# rev2.net
KiCad netlist of a schematic drawn in EAGLE
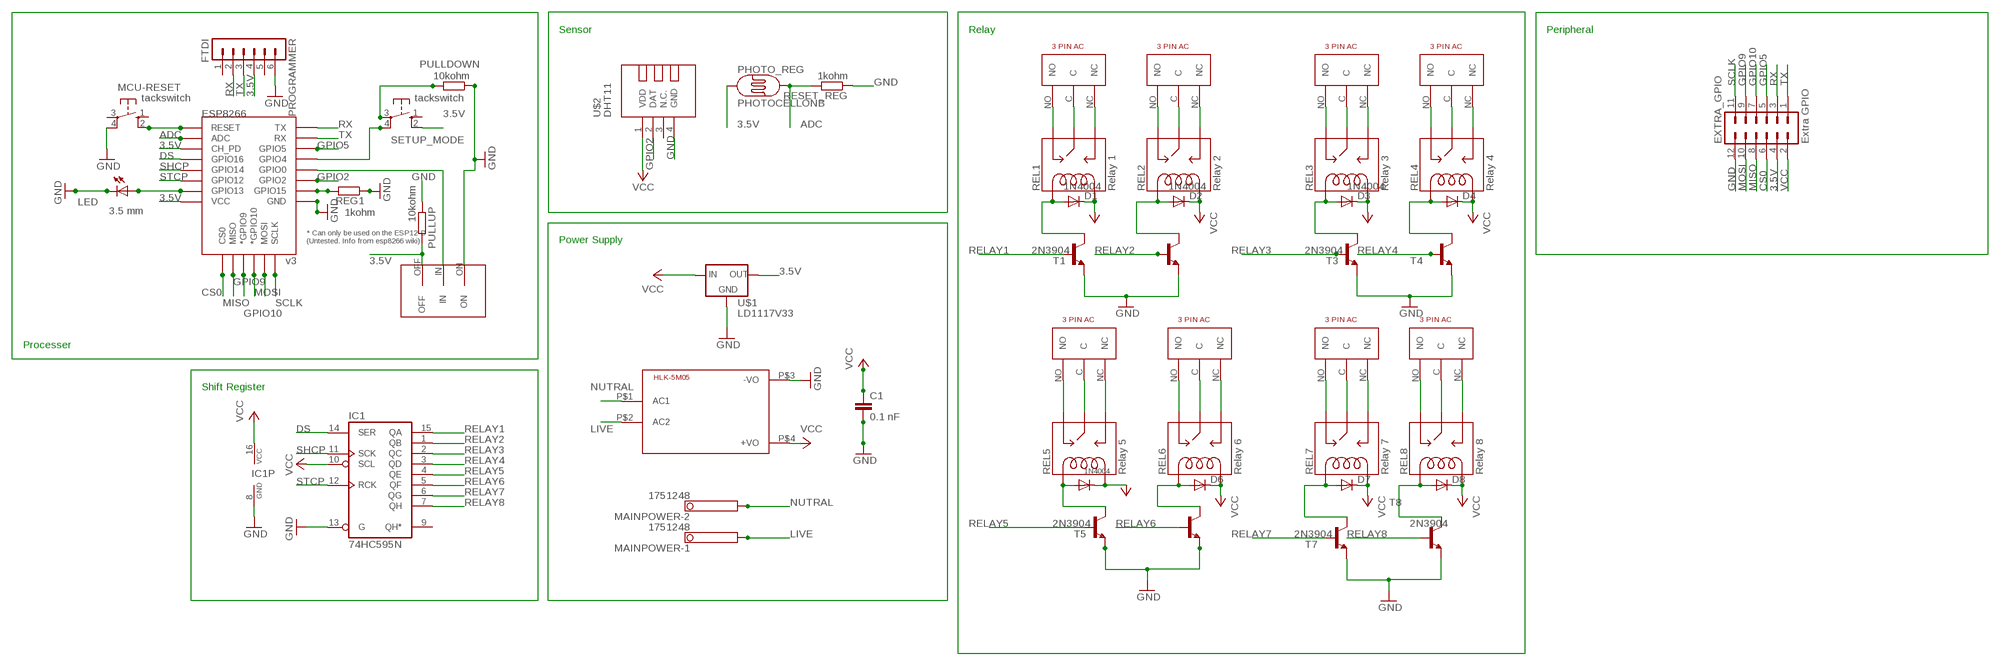
[diagram p0: schematic, sheet 1]

(export (version "E")
  (design (tool "Eeschema 10.0.6"))
  (components
    (comp (ref "C1")
      (value "0.1 nF")
      (footprint "eagle-import:CAP-PTH-SMALL-KIT")
      (libsource (lib "eagle-import") (part "0.1UF-KIT-EZ-50V-20%"))
    )
    (comp (ref "CON-REL-1")
      (value "3PINAC")
      (footprint "eagle-import:LIB")
      (libsource (lib "eagle-import") (part "3PINAC"))
    )
    (comp (ref "CON-REL-2")
      (value "3PINAC")
      (footprint "eagle-import:LIB")
      (libsource (lib "eagle-import") (part "3PINAC"))
    )
    (comp (ref "CON-REL-3")
      (value "3PINAC")
      (footprint "eagle-import:LIB")
      (libsource (lib "eagle-import") (part "3PINAC"))
    )
    (comp (ref "CON-REL-4")
      (value "3PINAC")
      (footprint "eagle-import:LIB")
      (libsource (lib "eagle-import") (part "3PINAC"))
    )
    (comp (ref "CON-REL-5")
      (value "3PINAC")
      (footprint "eagle-import:LIB")
      (libsource (lib "eagle-import") (part "3PINAC"))
    )
    (comp (ref "CON-REL-6")
      (value "3PINAC")
      (footprint "eagle-import:LIB")
      (libsource (lib "eagle-import") (part "3PINAC"))
    )
    (comp (ref "CON-REL-7")
      (value "3PINAC")
      (footprint "eagle-import:LIB")
      (libsource (lib "eagle-import") (part "3PINAC"))
    )
    (comp (ref "CON-REL-8")
      (value "3PINAC")
      (footprint "eagle-import:LIB")
      (libsource (lib "eagle-import") (part "3PINAC"))
    )
    (comp (ref "D1")
      (value "1N4004")
      (footprint "eagle-import:DO41-10")
      (libsource (lib "eagle-import") (part "1N4004"))
    )
    (comp (ref "D2")
      (value "1N4004")
      (footprint "eagle-import:DO41-10")
      (libsource (lib "eagle-import") (part "1N4004"))
    )
    (comp (ref "D3")
      (value "1N4004")
      (footprint "eagle-import:DO41-10")
      (libsource (lib "eagle-import") (part "1N4004"))
    )
    (comp (ref "D4")
      (value "1N4004")
      (footprint "eagle-import:DO41-10")
      (libsource (lib "eagle-import") (part "1N4004"))
    )
    (comp (ref "D5")
      (value "1N4004")
      (footprint "eagle-import:DO41-10")
      (libsource (lib "eagle-import") (part "1N4004"))
    )
    (comp (ref "D6")
      (value "1N4004")
      (footprint "eagle-import:DO41-10")
      (libsource (lib "eagle-import") (part "1N4004"))
    )
    (comp (ref "D7")
      (value "1N4004")
      (footprint "eagle-import:DO41-10")
      (libsource (lib "eagle-import") (part "1N4004"))
    )
    (comp (ref "D8")
      (value "1N4004")
      (footprint "eagle-import:DO41-10")
      (libsource (lib "eagle-import") (part "1N4004"))
    )
    (comp (ref "ESP8266")
      (value "v3")
      (footprint "eagle-import:ESP12E-SMD")
      (libsource (lib "eagle-import") (part "ESP12ESMD"))
    )
    (comp (ref "EXTRA_GPIO")
      (value "Extra GPIO")
      (footprint "eagle-import:MA06-2")
      (libsource (lib "eagle-import") (part "MA06-2"))
    )
    (comp (ref "FLASH")
      (value "TOGGLE_SWITCH")
      (footprint "eagle-import:TOGGLE_SWITCH")
      (libsource (lib "eagle-import") (part "TOGGLE_SWITCH"))
    )
    (comp (ref "HLK-5M05")
      (value "AC to DC Converter")
      (footprint "eagle-import:HKLPM01")
      (libsource (lib "eagle-import") (part "HKLPM01"))
    )
    (comp (ref "IC1")
      (value "74HC595N")
      (footprint "eagle-import:DIL16")
      (libsource (lib "eagle-import") (part "74595NHC"))
    )
    (comp (ref "LED")
      (value "3.5 mm")
      (footprint "eagle-import:LED3MM")
      (libsource (lib "eagle-import") (part "LED3MM"))
    )
    (comp (ref "MAINPOWER")
      (value "1751248")
      (footprint "eagle-import:1751248")
      (libsource (lib "eagle-import") (part "1751248"))
    )
    (comp (ref "MCU-RESET")
      (value "tackswitch")
      (footprint "eagle-import:B3F-10XX")
      (libsource (lib "eagle-import") (part "10-XX"))
    )
    (comp (ref "PHOTO_REG")
      (value "PHOTOCELLONB")
      (footprint "eagle-import:ON_BOARD")
      (libsource (lib "eagle-import") (part "PHOTOCELLONB"))
    )
    (comp (ref "PROGRAMMER")
      (value "FTDI")
      (footprint "eagle-import:MA06-1")
      (libsource (lib "eagle-import") (part "MA06-1"))
    )
    (comp (ref "PULLDOWN")
      (value "10kohm")
      (footprint "eagle-import:0204_7")
      (libsource (lib "eagle-import") (part "R-EU_0204/7"))
    )
    (comp (ref "PULLUP")
      (value "10kohm")
      (footprint "eagle-import:0204_7")
      (libsource (lib "eagle-import") (part "R-EU_0204/7"))
    )
    (comp (ref "REG1")
      (value "1kohm")
      (footprint "eagle-import:0204_7")
      (libsource (lib "eagle-import") (part "R-EU_0204/7"))
    )
    (comp (ref "REL1")
      (value "Relay 1")
      (footprint "eagle-import:SRD-05VDC-SL-C")
      (libsource (lib "eagle-import") (part "RELAYPTH"))
    )
    (comp (ref "REL2")
      (value "Relay 2")
      (footprint "eagle-import:SRD-05VDC-SL-C")
      (libsource (lib "eagle-import") (part "RELAYPTH"))
    )
    (comp (ref "REL3")
      (value "Relay 3")
      (footprint "eagle-import:SRD-05VDC-SL-C")
      (libsource (lib "eagle-import") (part "RELAYPTH"))
    )
    (comp (ref "REL4")
      (value "Relay 4")
      (footprint "eagle-import:SRD-05VDC-SL-C")
      (libsource (lib "eagle-import") (part "RELAYPTH"))
    )
    (comp (ref "REL5")
      (value "Relay 5")
      (footprint "eagle-import:SRD-05VDC-SL-C")
      (libsource (lib "eagle-import") (part "RELAYPTH"))
    )
    (comp (ref "REL6")
      (value "Relay 6")
      (footprint "eagle-import:SRD-05VDC-SL-C")
      (libsource (lib "eagle-import") (part "RELAYPTH"))
    )
    (comp (ref "REL7")
      (value "Relay 7")
      (footprint "eagle-import:SRD-05VDC-SL-C")
      (libsource (lib "eagle-import") (part "RELAYPTH"))
    )
    (comp (ref "REL8")
      (value "Relay 8")
      (footprint "eagle-import:SRD-05VDC-SL-C")
      (libsource (lib "eagle-import") (part "RELAYPTH"))
    )
    (comp (ref "RESET_REG")
      (value "1kohm")
      (footprint "eagle-import:0204_7")
      (libsource (lib "eagle-import") (part "R-EU_0204/7"))
    )
    (comp (ref "SETUP_MODE")
      (value "tackswitch")
      (footprint "eagle-import:B3F-10XX")
      (libsource (lib "eagle-import") (part "10-XX"))
    )
    (comp (ref "T1")
      (value "2N3904")
      (footprint "eagle-import:TO92-EBC")
      (libsource (lib "eagle-import") (part "BC618"))
    )
    (comp (ref "T2")
      (value "2N3904")
      (footprint "eagle-import:TO92-EBC")
      (libsource (lib "eagle-import") (part "BC618"))
    )
    (comp (ref "T3")
      (value "2N3904")
      (footprint "eagle-import:TO92-EBC")
      (libsource (lib "eagle-import") (part "BC618"))
    )
    (comp (ref "T4")
      (value "2N3904")
      (footprint "eagle-import:TO92-EBC")
      (libsource (lib "eagle-import") (part "BC618"))
    )
    (comp (ref "T5")
      (value "2N3904")
      (footprint "eagle-import:TO92-EBC")
      (libsource (lib "eagle-import") (part "BC618"))
    )
    (comp (ref "T6")
      (value "2N3904")
      (footprint "eagle-import:TO92-EBC")
      (libsource (lib "eagle-import") (part "BC618"))
    )
    (comp (ref "T7")
      (value "2N3904")
      (footprint "eagle-import:TO92-EBC")
      (libsource (lib "eagle-import") (part "BC618"))
    )
    (comp (ref "T8")
      (value "2N3904")
      (footprint "eagle-import:TO92-EBC")
      (libsource (lib "eagle-import") (part "BC618"))
    )
    (comp (ref "U$1")
      (value "LD1117V33")
      (footprint "eagle-import:LD1117V33")
      (libsource (lib "eagle-import") (part "LD1117V33"))
    )
    (comp (ref "U$2")
      (value "DHT11")
      (footprint "eagle-import:TEMP-HUM-SENSOR-DHT11")
      (libsource (lib "eagle-import") (part "TEMP-HUM-SENSOR-DHT11"))
    )
  )
  (nets
    (net (code "1") (name "/3.5V") (class "Default")
      (node (ref "ESP8266") (pin "CH_PD") (pinfunction "CH_PD_CH_PD") (pintype "bidirectional"))
      (node (ref "ESP8266") (pin "VCC") (pinfunction "VCC_VCC") (pintype "bidirectional"))
      (node (ref "EXTRA_GPIO") (pin "4") (pinfunction "4_4") (pintype "passive"))
      (node (ref "FLASH") (pin "OFF") (pinfunction "OFF_OFF") (pintype "bidirectional"))
      (node (ref "PHOTO_REG") (pin "1") (pinfunction "P$1_1") (pintype "bidirectional"))
      (node (ref "PROGRAMMER") (pin "4") (pinfunction "4_4") (pintype "passive"))
      (node (ref "PULLUP") (pin "2") (pinfunction "2_2") (pintype "passive"))
      (node (ref "SETUP_MODE") (pin "2") (pinfunction "S1_2") (pintype "passive"))
      (node (ref "U$1") (pin "OUT") (pinfunction "OUT_OUT") (pintype "output"))
    )
    (net (code "2") (name "/ADC") (class "Default")
      (node (ref "ESP8266") (pin "ADC") (pinfunction "ADC_ADC") (pintype "bidirectional"))
      (node (ref "PHOTO_REG") (pin "2") (pinfunction "P$2_2") (pintype "bidirectional"))
      (node (ref "RESET_REG") (pin "2") (pinfunction "2_2") (pintype "passive"))
    )
    (net (code "3") (name "/CS0") (class "Default")
      (node (ref "ESP8266") (pin "CS0") (pinfunction "CS0_CS0") (pintype "bidirectional"))
      (node (ref "EXTRA_GPIO") (pin "6") (pinfunction "6_6") (pintype "passive"))
    )
    (net (code "4") (name "/DS") (class "Default")
      (node (ref "ESP8266") (pin "GPIO16") (pinfunction "GPIO16_GPIO16") (pintype "bidirectional"))
      (node (ref "IC1") (pin "14") (pinfunction "SER_14") (pintype "input"))
    )
    (net (code "5") (name "/GPIO2") (class "Default")
      (node (ref "ESP8266") (pin "GPIO2") (pinfunction "GPIO2_GPIO2") (pintype "bidirectional"))
      (node (ref "U$2") (pin "2") (pinfunction "DAT_2") (pintype "bidirectional"))
    )
    (net (code "6") (name "/GPIO5") (class "Default")
      (node (ref "ESP8266") (pin "GPIO5") (pinfunction "GPIO5_GPIO5") (pintype "bidirectional"))
      (node (ref "EXTRA_GPIO") (pin "5") (pinfunction "5_5") (pintype "passive"))
    )
    (net (code "7") (name "/GPIO9") (class "Default")
      (node (ref "ESP8266") (pin "GPIO9") (pinfunction "*GPIO9_GPIO9") (pintype "bidirectional"))
      (node (ref "EXTRA_GPIO") (pin "9") (pinfunction "9_9") (pintype "passive"))
    )
    (net (code "8") (name "/GPIO10") (class "Default")
      (node (ref "ESP8266") (pin "GPIO10") (pinfunction "*GPIO10_GPIO10") (pintype "bidirectional"))
      (node (ref "EXTRA_GPIO") (pin "7") (pinfunction "7_7") (pintype "passive"))
    )
    (net (code "9") (name "/LIVE") (class "Default")
      (node (ref "HLK-5M05") (pin "P$2") (pinfunction "AC2_P$2") (pintype "bidirectional"))
      (node (ref "MAINPOWER") (pin "1") (pinfunction "K_1") (pintype "passive"))
    )
    (net (code "10") (name "/MISO") (class "Default")
      (node (ref "ESP8266") (pin "MISO") (pinfunction "MISO_MISO") (pintype "bidirectional"))
      (node (ref "EXTRA_GPIO") (pin "8") (pinfunction "8_8") (pintype "passive"))
    )
    (net (code "11") (name "/MOSI") (class "Default")
      (node (ref "ESP8266") (pin "MOSI") (pinfunction "MOSI_MOSI") (pintype "bidirectional"))
      (node (ref "EXTRA_GPIO") (pin "10") (pinfunction "10_10") (pintype "passive"))
    )
    (net (code "12") (name "/NUTRAL") (class "Default")
      (node (ref "HLK-5M05") (pin "P$1") (pinfunction "AC1_P$1") (pintype "bidirectional"))
      (node (ref "MAINPOWER") (pin "2") (pinfunction "K_2") (pintype "passive"))
    )
    (net (code "13") (name "/RELAY1") (class "Default")
      (node (ref "IC1") (pin "15") (pinfunction "QA_15") (pintype "tri_state"))
      (node (ref "T1") (pin "B") (pinfunction "B_B") (pintype "passive"))
    )
    (net (code "14") (name "/RELAY2") (class "Default")
      (node (ref "IC1") (pin "1") (pinfunction "QB_1") (pintype "tri_state"))
      (node (ref "T2") (pin "B") (pinfunction "B_B") (pintype "passive"))
    )
    (net (code "15") (name "/RELAY3") (class "Default")
      (node (ref "IC1") (pin "2") (pinfunction "QC_2") (pintype "tri_state"))
      (node (ref "T3") (pin "B") (pinfunction "B_B") (pintype "passive"))
    )
    (net (code "16") (name "/RELAY4") (class "Default")
      (node (ref "IC1") (pin "3") (pinfunction "QD_3") (pintype "tri_state"))
      (node (ref "T4") (pin "B") (pinfunction "B_B") (pintype "passive"))
    )
    (net (code "17") (name "/RELAY5") (class "Default")
      (node (ref "IC1") (pin "4") (pinfunction "QE_4") (pintype "tri_state"))
      (node (ref "T5") (pin "B") (pinfunction "B_B") (pintype "passive"))
    )
    (net (code "18") (name "/RELAY6") (class "Default")
      (node (ref "IC1") (pin "5") (pinfunction "QF_5") (pintype "tri_state"))
      (node (ref "T6") (pin "B") (pinfunction "B_B") (pintype "passive"))
    )
    (net (code "19") (name "/RELAY7") (class "Default")
      (node (ref "IC1") (pin "6") (pinfunction "QG_6") (pintype "tri_state"))
      (node (ref "T7") (pin "B") (pinfunction "B_B") (pintype "passive"))
    )
    (net (code "20") (name "/RELAY8") (class "Default")
      (node (ref "IC1") (pin "7") (pinfunction "QH_7") (pintype "tri_state"))
      (node (ref "T8") (pin "B") (pinfunction "B_B") (pintype "passive"))
    )
    (net (code "21") (name "/RX") (class "Default")
      (node (ref "ESP8266") (pin "TXD0") (pinfunction "TX_TXD0") (pintype "bidirectional"))
      (node (ref "EXTRA_GPIO") (pin "3") (pinfunction "3_3") (pintype "passive"))
      (node (ref "PROGRAMMER") (pin "2") (pinfunction "2_2") (pintype "passive"))
    )
    (net (code "22") (name "/SCLK") (class "Default")
      (node (ref "ESP8266") (pin "SCLK") (pinfunction "SCLK_SCLK") (pintype "bidirectional"))
      (node (ref "EXTRA_GPIO") (pin "11") (pinfunction "11_11") (pintype "passive"))
    )
    (net (code "23") (name "/SHCP") (class "Default")
      (node (ref "ESP8266") (pin "GPIO14") (pinfunction "GPIO14_GPIO14") (pintype "bidirectional"))
      (node (ref "IC1") (pin "11") (pinfunction "SCK_11") (pintype "input"))
    )
    (net (code "24") (name "/STCP") (class "Default")
      (node (ref "ESP8266") (pin "GPIO12") (pinfunction "GPIO12_GPIO12") (pintype "bidirectional"))
      (node (ref "IC1") (pin "12") (pinfunction "RCK_12") (pintype "input"))
    )
    (net (code "25") (name "/TX") (class "Default")
      (node (ref "ESP8266") (pin "RXD0") (pinfunction "RX_RXD0") (pintype "bidirectional"))
      (node (ref "EXTRA_GPIO") (pin "1") (pinfunction "1_1") (pintype "passive"))
      (node (ref "PROGRAMMER") (pin "3") (pinfunction "3_3") (pintype "passive"))
    )
    (net (code "26") (name "GND") (class "Default")
      (node (ref "C1") (pin "2") (pinfunction "2_2") (pintype "passive"))
      (node (ref "ESP8266") (pin "GND") (pinfunction "GND_GND") (pintype "bidirectional"))
      (node (ref "EXTRA_GPIO") (pin "12") (pinfunction "12_12") (pintype "passive"))
      (node (ref "FLASH") (pin "ON") (pinfunction "ON_ON") (pintype "bidirectional"))
      (node (ref "HLK-5M05") (pin "P$3") (pinfunction "-VO_P$3") (pintype "bidirectional"))
      (node (ref "IC1") (pin "13") (pinfunction "G_13") (pintype "input"))
      (node (ref "IC1") (pin "8") (pinfunction "GND_8") (pintype "power_in"))
      (node (ref "LED") (pin "K") (pinfunction "C_K") (pintype "passive"))
      (node (ref "MCU-RESET") (pin "4") (pinfunction "P1_4") (pintype "passive"))
      (node (ref "PROGRAMMER") (pin "6") (pinfunction "6_6") (pintype "passive"))
      (node (ref "PULLDOWN") (pin "1") (pinfunction "1_1") (pintype "passive"))
      (node (ref "PULLUP") (pin "1") (pinfunction "1_1") (pintype "passive"))
      (node (ref "REG1") (pin "1") (pinfunction "1_1") (pintype "passive"))
      (node (ref "RESET_REG") (pin "1") (pinfunction "1_1") (pintype "passive"))
      (node (ref "T1") (pin "E") (pinfunction "E_E") (pintype "passive"))
      (node (ref "T2") (pin "E") (pinfunction "E_E") (pintype "passive"))
      (node (ref "T3") (pin "E") (pinfunction "E_E") (pintype "passive"))
      (node (ref "T4") (pin "E") (pinfunction "E_E") (pintype "passive"))
      (node (ref "T5") (pin "E") (pinfunction "E_E") (pintype "passive"))
      (node (ref "T6") (pin "E") (pinfunction "E_E") (pintype "passive"))
      (node (ref "T7") (pin "E") (pinfunction "E_E") (pintype "passive"))
      (node (ref "T8") (pin "E") (pinfunction "E_E") (pintype "passive"))
      (node (ref "U$1") (pin "GND") (pinfunction "GND_GND") (pintype "input"))
      (node (ref "U$2") (pin "4") (pinfunction "GND_4") (pintype "power_in"))
    )
    (net (code "27") (name "Net-(CON-REL-1-PadC)") (class "Default")
      (node (ref "CON-REL-1") (pin "C") (pinfunction "C_C") (pintype "bidirectional"))
      (node (ref "REL1") (pin "SWCOMMON") (pinfunction "SWCOMMON_SWCOMMON") (pintype "bidirectional"))
    )
    (net (code "28") (name "Net-(CON-REL-1-PadNC)") (class "Default")
      (node (ref "CON-REL-1") (pin "NC") (pinfunction "NC_NC") (pintype "bidirectional"))
      (node (ref "REL1") (pin "SWOPEN") (pinfunction "SWOPEN_SWOPEN") (pintype "bidirectional"))
    )
    (net (code "29") (name "Net-(CON-REL-2-PadC)") (class "Default")
      (node (ref "CON-REL-2") (pin "C") (pinfunction "C_C") (pintype "bidirectional"))
      (node (ref "REL2") (pin "SWCOMMON") (pinfunction "SWCOMMON_SWCOMMON") (pintype "bidirectional"))
    )
    (net (code "30") (name "Net-(CON-REL-2-PadNC)") (class "Default")
      (node (ref "CON-REL-2") (pin "NC") (pinfunction "NC_NC") (pintype "bidirectional"))
      (node (ref "REL2") (pin "SWOPEN") (pinfunction "SWOPEN_SWOPEN") (pintype "bidirectional"))
    )
    (net (code "31") (name "Net-(CON-REL-3-PadC)") (class "Default")
      (node (ref "CON-REL-3") (pin "C") (pinfunction "C_C") (pintype "bidirectional"))
      (node (ref "REL3") (pin "SWCOMMON") (pinfunction "SWCOMMON_SWCOMMON") (pintype "bidirectional"))
    )
    (net (code "32") (name "Net-(CON-REL-3-PadNC)") (class "Default")
      (node (ref "CON-REL-3") (pin "NC") (pinfunction "NC_NC") (pintype "bidirectional"))
      (node (ref "REL3") (pin "SWOPEN") (pinfunction "SWOPEN_SWOPEN") (pintype "bidirectional"))
    )
    (net (code "33") (name "Net-(CON-REL-4-PadC)") (class "Default")
      (node (ref "CON-REL-4") (pin "C") (pinfunction "C_C") (pintype "bidirectional"))
      (node (ref "REL4") (pin "SWCOMMON") (pinfunction "SWCOMMON_SWCOMMON") (pintype "bidirectional"))
    )
    (net (code "34") (name "Net-(CON-REL-4-PadNC)") (class "Default")
      (node (ref "CON-REL-4") (pin "NC") (pinfunction "NC_NC") (pintype "bidirectional"))
      (node (ref "REL4") (pin "SWOPEN") (pinfunction "SWOPEN_SWOPEN") (pintype "bidirectional"))
    )
    (net (code "35") (name "Net-(CON-REL-5-PadC)") (class "Default")
      (node (ref "CON-REL-5") (pin "C") (pinfunction "C_C") (pintype "bidirectional"))
      (node (ref "REL5") (pin "SWCOMMON") (pinfunction "SWCOMMON_SWCOMMON") (pintype "bidirectional"))
    )
    (net (code "36") (name "Net-(CON-REL-5-PadNC)") (class "Default")
      (node (ref "CON-REL-5") (pin "NC") (pinfunction "NC_NC") (pintype "bidirectional"))
      (node (ref "REL5") (pin "SWOPEN") (pinfunction "SWOPEN_SWOPEN") (pintype "bidirectional"))
    )
    (net (code "37") (name "Net-(CON-REL-6-PadC)") (class "Default")
      (node (ref "CON-REL-6") (pin "C") (pinfunction "C_C") (pintype "bidirectional"))
      (node (ref "REL6") (pin "SWCOMMON") (pinfunction "SWCOMMON_SWCOMMON") (pintype "bidirectional"))
    )
    (net (code "38") (name "Net-(CON-REL-6-PadNC)") (class "Default")
      (node (ref "CON-REL-6") (pin "NC") (pinfunction "NC_NC") (pintype "bidirectional"))
      (node (ref "REL6") (pin "SWOPEN") (pinfunction "SWOPEN_SWOPEN") (pintype "bidirectional"))
    )
    (net (code "39") (name "Net-(CON-REL-7-PadC)") (class "Default")
      (node (ref "CON-REL-7") (pin "C") (pinfunction "C_C") (pintype "bidirectional"))
      (node (ref "REL7") (pin "SWCOMMON") (pinfunction "SWCOMMON_SWCOMMON") (pintype "bidirectional"))
    )
    (net (code "40") (name "Net-(CON-REL-7-PadNC)") (class "Default")
      (node (ref "CON-REL-7") (pin "NC") (pinfunction "NC_NC") (pintype "bidirectional"))
      (node (ref "REL7") (pin "SWOPEN") (pinfunction "SWOPEN_SWOPEN") (pintype "bidirectional"))
    )
    (net (code "41") (name "Net-(CON-REL-8-PadC)") (class "Default")
      (node (ref "CON-REL-8") (pin "C") (pinfunction "C_C") (pintype "bidirectional"))
      (node (ref "REL8") (pin "SWCOMMON") (pinfunction "SWCOMMON_SWCOMMON") (pintype "bidirectional"))
    )
    (net (code "42") (name "Net-(CON-REL-8-PadNC)") (class "Default")
      (node (ref "CON-REL-8") (pin "NC") (pinfunction "NC_NC") (pintype "bidirectional"))
      (node (ref "REL8") (pin "SWOPEN") (pinfunction "SWOPEN_SWOPEN") (pintype "bidirectional"))
    )
    (net (code "43") (name "Net-(D1-PadA)") (class "Default")
      (node (ref "D1") (pin "A") (pinfunction "A_A") (pintype "passive"))
      (node (ref "REL1") (pin "COIL1") (pinfunction "COIL1_COIL1") (pintype "bidirectional"))
      (node (ref "T1") (pin "C") (pinfunction "C_C") (pintype "passive"))
    )
    (net (code "44") (name "Net-(D2-PadA)") (class "Default")
      (node (ref "D2") (pin "A") (pinfunction "A_A") (pintype "passive"))
      (node (ref "REL2") (pin "COIL1") (pinfunction "COIL1_COIL1") (pintype "bidirectional"))
      (node (ref "T2") (pin "C") (pinfunction "C_C") (pintype "passive"))
    )
    (net (code "45") (name "Net-(D3-PadA)") (class "Default")
      (node (ref "D3") (pin "A") (pinfunction "A_A") (pintype "passive"))
      (node (ref "REL3") (pin "COIL1") (pinfunction "COIL1_COIL1") (pintype "bidirectional"))
      (node (ref "T3") (pin "C") (pinfunction "C_C") (pintype "passive"))
    )
    (net (code "46") (name "Net-(D4-PadA)") (class "Default")
      (node (ref "D4") (pin "A") (pinfunction "A_A") (pintype "passive"))
      (node (ref "REL4") (pin "COIL1") (pinfunction "COIL1_COIL1") (pintype "bidirectional"))
      (node (ref "T4") (pin "C") (pinfunction "C_C") (pintype "passive"))
    )
    (net (code "47") (name "Net-(D5-PadA)") (class "Default")
      (node (ref "D5") (pin "A") (pinfunction "A_A") (pintype "passive"))
      (node (ref "REL5") (pin "COIL1") (pinfunction "COIL1_COIL1") (pintype "bidirectional"))
      (node (ref "T5") (pin "C") (pinfunction "C_C") (pintype "passive"))
    )
    (net (code "48") (name "Net-(D6-PadA)") (class "Default")
      (node (ref "D6") (pin "A") (pinfunction "A_A") (pintype "passive"))
      (node (ref "REL6") (pin "COIL1") (pinfunction "COIL1_COIL1") (pintype "bidirectional"))
      (node (ref "T6") (pin "C") (pinfunction "C_C") (pintype "passive"))
    )
    (net (code "49") (name "Net-(D7-PadA)") (class "Default")
      (node (ref "D7") (pin "A") (pinfunction "A_A") (pintype "passive"))
      (node (ref "REL7") (pin "COIL1") (pinfunction "COIL1_COIL1") (pintype "bidirectional"))
      (node (ref "T7") (pin "C") (pinfunction "C_C") (pintype "passive"))
    )
    (net (code "50") (name "Net-(D8-PadA)") (class "Default")
      (node (ref "D8") (pin "A") (pinfunction "A_A") (pintype "passive"))
      (node (ref "REL8") (pin "COIL1") (pinfunction "COIL1_COIL1") (pintype "bidirectional"))
      (node (ref "T8") (pin "C") (pinfunction "C_C") (pintype "passive"))
    )
    (net (code "51") (name "Net-(ESP8266-PadGPIO0)") (class "Default")
      (node (ref "ESP8266") (pin "GPIO0") (pinfunction "GPIO0_GPIO0") (pintype "bidirectional"))
      (node (ref "FLASH") (pin "IN") (pinfunction "IN_IN") (pintype "bidirectional"))
    )
    (net (code "52") (name "Net-(ESP8266-PadGPIO13)") (class "Default")
      (node (ref "ESP8266") (pin "GPIO13") (pinfunction "GPIO13_GPIO13") (pintype "bidirectional"))
      (node (ref "LED") (pin "A") (pinfunction "A_A") (pintype "passive"))
    )
    (net (code "53") (name "Net-(ESP8266-PadGPIO15)") (class "Default")
      (node (ref "ESP8266") (pin "GPIO15") (pinfunction "GPIO15_GPIO15") (pintype "bidirectional"))
      (node (ref "REG1") (pin "2") (pinfunction "2_2") (pintype "passive"))
    )
    (net (code "54") (name "Net-(MCU-RESET-S1)") (class "Default")
      (node (ref "ESP8266") (pin "RESET") (pinfunction "RESET_RESET") (pintype "bidirectional"))
      (node (ref "MCU-RESET") (pin "2") (pinfunction "S1_2") (pintype "passive"))
    )
    (net (code "55") (name "Net-(REL1-SWCLOSE)") (class "Default")
      (node (ref "CON-REL-1") (pin "NO") (pinfunction "NO_NO") (pintype "bidirectional"))
      (node (ref "REL1") (pin "SWCLOSED") (pinfunction "SWCLOSE_SWCLOSED") (pintype "bidirectional"))
    )
    (net (code "56") (name "Net-(REL2-SWCLOSE)") (class "Default")
      (node (ref "CON-REL-2") (pin "NO") (pinfunction "NO_NO") (pintype "bidirectional"))
      (node (ref "REL2") (pin "SWCLOSED") (pinfunction "SWCLOSE_SWCLOSED") (pintype "bidirectional"))
    )
    (net (code "57") (name "Net-(REL3-SWCLOSE)") (class "Default")
      (node (ref "CON-REL-3") (pin "NO") (pinfunction "NO_NO") (pintype "bidirectional"))
      (node (ref "REL3") (pin "SWCLOSED") (pinfunction "SWCLOSE_SWCLOSED") (pintype "bidirectional"))
    )
    (net (code "58") (name "Net-(REL4-SWCLOSE)") (class "Default")
      (node (ref "CON-REL-4") (pin "NO") (pinfunction "NO_NO") (pintype "bidirectional"))
      (node (ref "REL4") (pin "SWCLOSED") (pinfunction "SWCLOSE_SWCLOSED") (pintype "bidirectional"))
    )
    (net (code "59") (name "Net-(REL5-SWCLOSE)") (class "Default")
      (node (ref "CON-REL-5") (pin "NO") (pinfunction "NO_NO") (pintype "bidirectional"))
      (node (ref "REL5") (pin "SWCLOSED") (pinfunction "SWCLOSE_SWCLOSED") (pintype "bidirectional"))
    )
    (net (code "60") (name "Net-(REL6-SWCLOSE)") (class "Default")
      (node (ref "CON-REL-6") (pin "NO") (pinfunction "NO_NO") (pintype "bidirectional"))
      (node (ref "REL6") (pin "SWCLOSED") (pinfunction "SWCLOSE_SWCLOSED") (pintype "bidirectional"))
    )
    (net (code "61") (name "Net-(REL7-SWCLOSE)") (class "Default")
      (node (ref "CON-REL-7") (pin "NO") (pinfunction "NO_NO") (pintype "bidirectional"))
      (node (ref "REL7") (pin "SWCLOSED") (pinfunction "SWCLOSE_SWCLOSED") (pintype "bidirectional"))
    )
    (net (code "62") (name "Net-(REL8-SWCLOSE)") (class "Default")
      (node (ref "CON-REL-8") (pin "NO") (pinfunction "NO_NO") (pintype "bidirectional"))
      (node (ref "REL8") (pin "SWCLOSED") (pinfunction "SWCLOSE_SWCLOSED") (pintype "bidirectional"))
    )
    (net (code "63") (name "Net-(SETUP_MODE-P)") (class "Default")
      (node (ref "PULLDOWN") (pin "2") (pinfunction "2_2") (pintype "passive"))
      (node (ref "SETUP_MODE") (pin "3") (pinfunction "P_3") (pintype "passive"))
    )
    (net (code "64") (name "Net-(SETUP_MODE-P1)") (class "Default")
      (node (ref "ESP8266") (pin "GPIO4") (pinfunction "GPIO4_GPIO4") (pintype "bidirectional"))
      (node (ref "SETUP_MODE") (pin "4") (pinfunction "P1_4") (pintype "passive"))
    )
    (net (code "65") (name "VCC") (class "Default")
      (node (ref "C1") (pin "1") (pinfunction "1_1") (pintype "passive"))
      (node (ref "D1") (pin "C") (pinfunction "C_C") (pintype "passive"))
      (node (ref "D2") (pin "C") (pinfunction "C_C") (pintype "passive"))
      (node (ref "D3") (pin "C") (pinfunction "C_C") (pintype "passive"))
      (node (ref "D4") (pin "C") (pinfunction "C_C") (pintype "passive"))
      (node (ref "D5") (pin "C") (pinfunction "C_C") (pintype "passive"))
      (node (ref "D6") (pin "C") (pinfunction "C_C") (pintype "passive"))
      (node (ref "D7") (pin "C") (pinfunction "C_C") (pintype "passive"))
      (node (ref "D8") (pin "C") (pinfunction "C_C") (pintype "passive"))
      (node (ref "EXTRA_GPIO") (pin "2") (pinfunction "2_2") (pintype "passive"))
      (node (ref "HLK-5M05") (pin "P$4") (pinfunction "+VO_P$4") (pintype "bidirectional"))
      (node (ref "IC1") (pin "10") (pinfunction "SCL_10") (pintype "input"))
      (node (ref "IC1") (pin "16") (pinfunction "VCC_16") (pintype "power_in"))
      (node (ref "REL1") (pin "COIL0") (pinfunction "COIL0_COIL0") (pintype "bidirectional"))
      (node (ref "REL2") (pin "COIL0") (pinfunction "COIL0_COIL0") (pintype "bidirectional"))
      (node (ref "REL3") (pin "COIL0") (pinfunction "COIL0_COIL0") (pintype "bidirectional"))
      (node (ref "REL4") (pin "COIL0") (pinfunction "COIL0_COIL0") (pintype "bidirectional"))
      (node (ref "REL5") (pin "COIL0") (pinfunction "COIL0_COIL0") (pintype "bidirectional"))
      (node (ref "REL6") (pin "COIL0") (pinfunction "COIL0_COIL0") (pintype "bidirectional"))
      (node (ref "REL7") (pin "COIL0") (pinfunction "COIL0_COIL0") (pintype "bidirectional"))
      (node (ref "REL8") (pin "COIL0") (pinfunction "COIL0_COIL0") (pintype "bidirectional"))
      (node (ref "U$1") (pin "IN") (pinfunction "IN_IN") (pintype "input"))
      (node (ref "U$2") (pin "1") (pinfunction "VDD_1") (pintype "power_in"))
    )
    (net (code "66") (name "unconnected-(IC1A-QH*-Pad9)") (class "Default")
      (node (ref "IC1") (pin "9") (pinfunction "QH*_9") (pintype "tri_state"))
    )
    (net (code "67") (name "unconnected-(MCU-RESET-P-Pad3)") (class "Default")
      (node (ref "MCU-RESET") (pin "3") (pinfunction "P_3") (pintype "passive"))
    )
    (net (code "68") (name "unconnected-(MCU-RESET-S-Pad1)") (class "Default")
      (node (ref "MCU-RESET") (pin "1") (pinfunction "S_1") (pintype "passive"))
    )
    (net (code "69") (name "unconnected-(PROGRAMMER-Pad1)") (class "Default")
      (node (ref "PROGRAMMER") (pin "1") (pinfunction "1_1") (pintype "passive"))
    )
    (net (code "70") (name "unconnected-(PROGRAMMER-Pad5)") (class "Default")
      (node (ref "PROGRAMMER") (pin "5") (pinfunction "5_5") (pintype "passive"))
    )
    (net (code "71") (name "unconnected-(SETUP_MODE-S-Pad1)") (class "Default")
      (node (ref "SETUP_MODE") (pin "1") (pinfunction "S_1") (pintype "passive"))
    )
    (net (code "72") (name "unconnected-(U$2-N.C.-Pad3)") (class "Default")
      (node (ref "U$2") (pin "3") (pinfunction "N.C._3") (pintype "passive"))
    )
  )
)
